# CH32V407RET-R0.net
KiCad netlist of a schematic drawn in Altium Designer
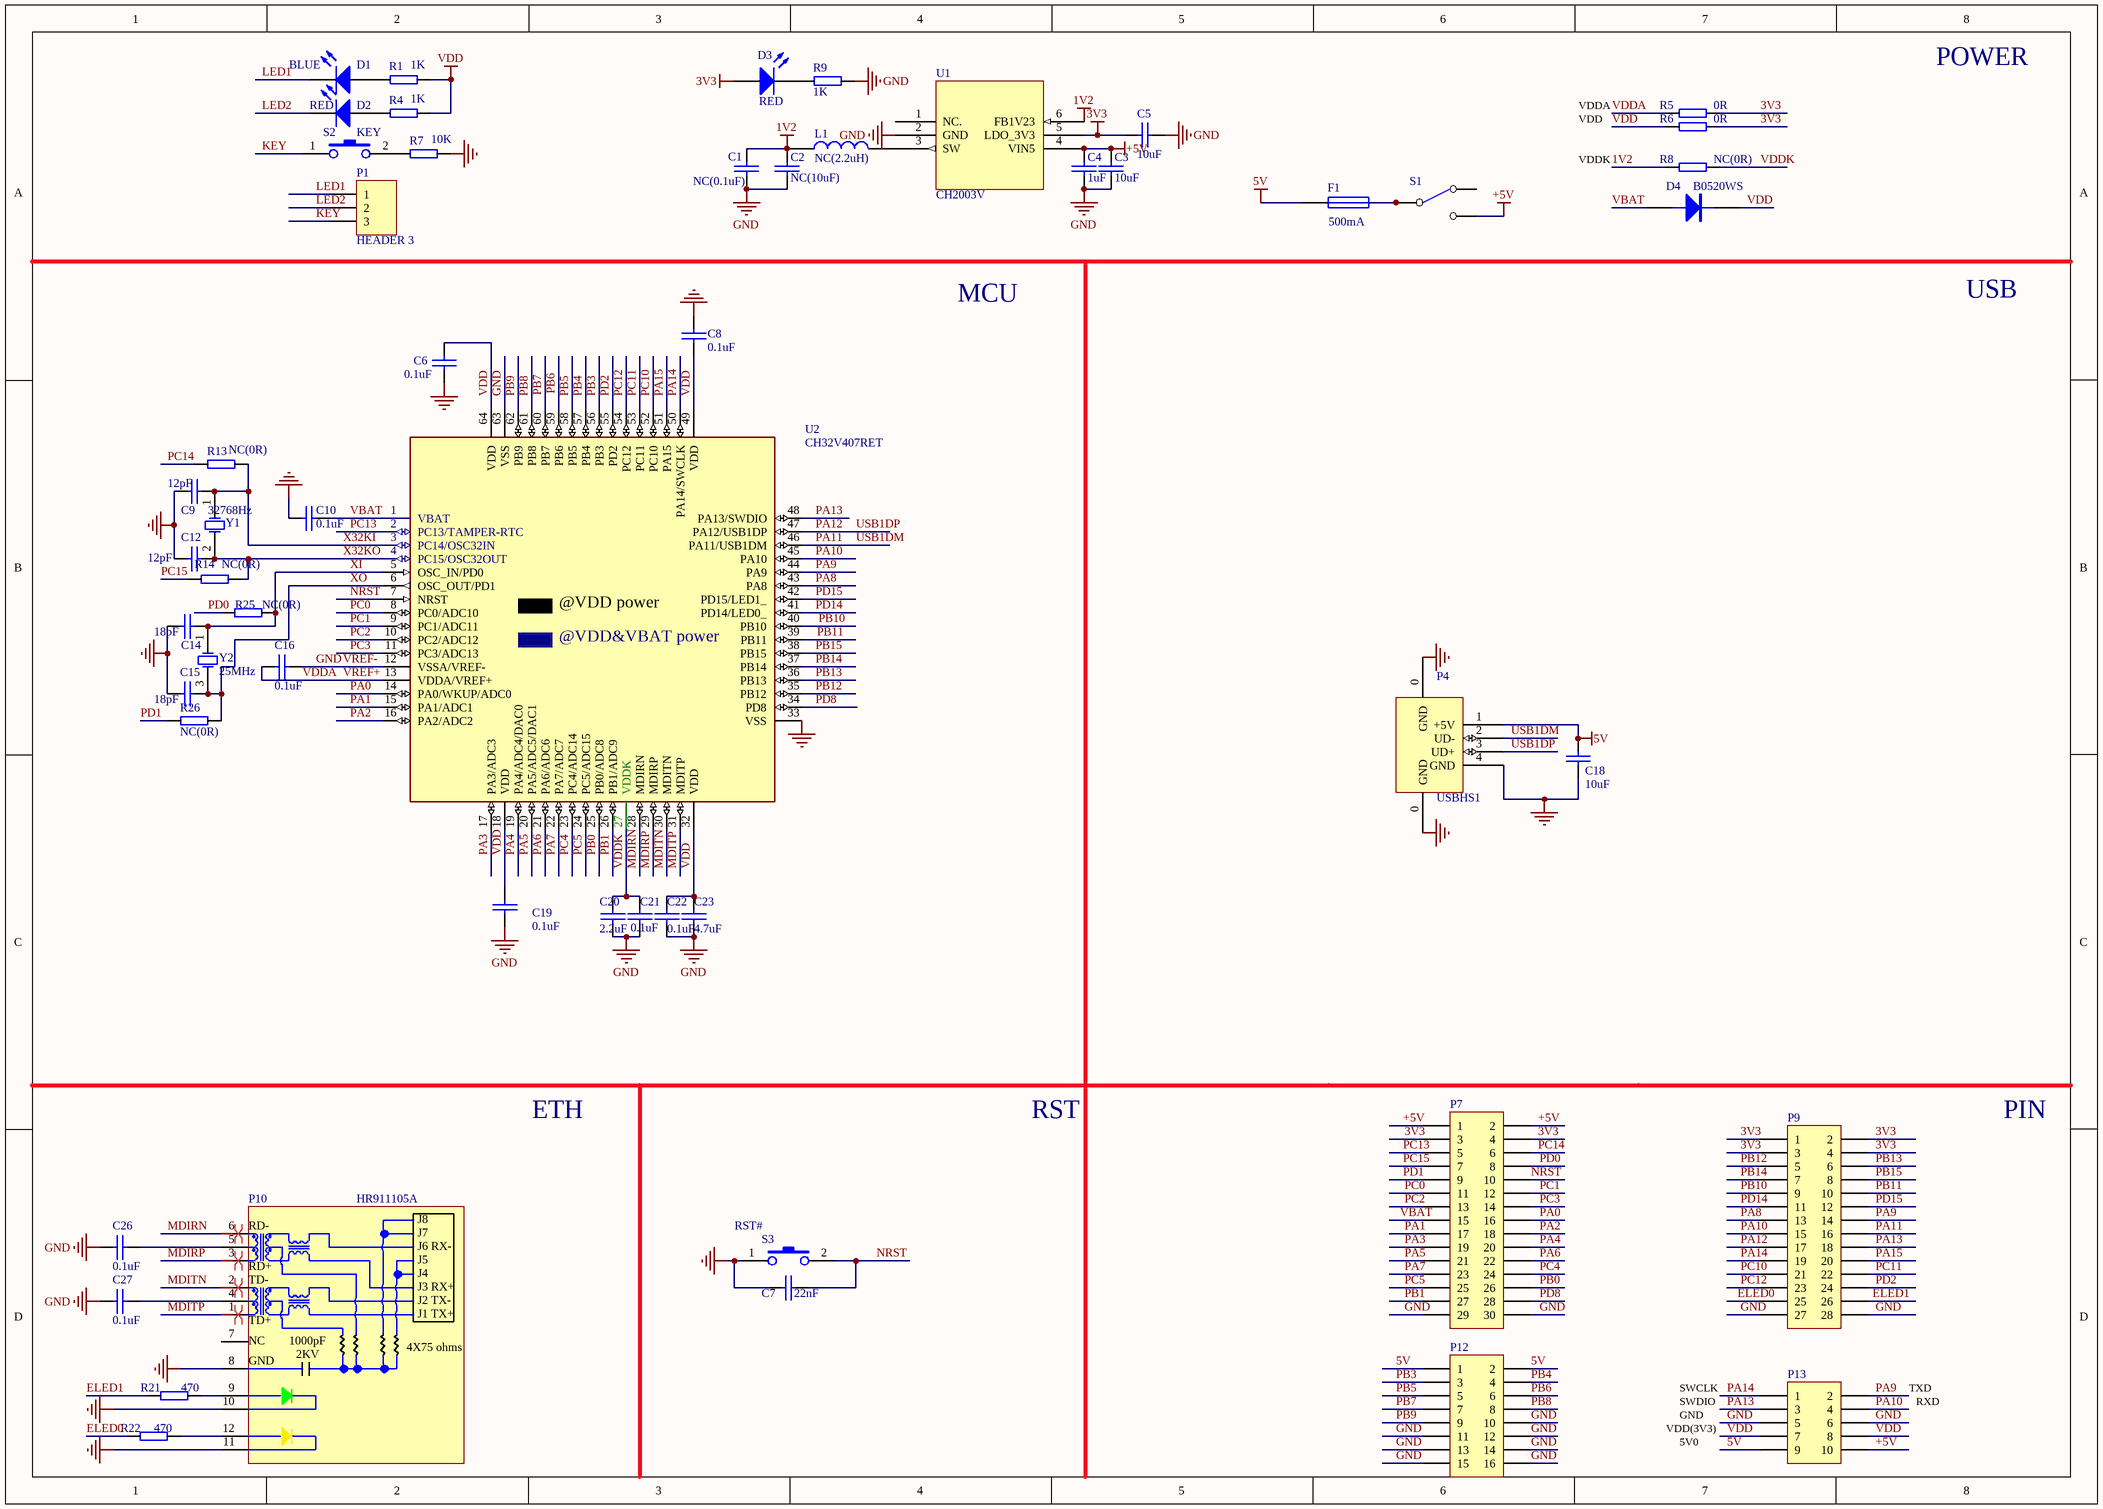
[diagram p0: CH32V407RET-R0.SchDoc]

(export (version "E")
  (design (tool "Eeschema 10.0.6"))
  (components
    (comp (ref "C1")
      (value "NC(0.1uF)")
      (footprint "0402_C")
      (description "Capacitor")
      (libsource (lib "") (part "CAP_2"))
    )
    (comp (ref "C2")
      (value "NC(10uF)")
      (footprint "0603_C")
      (description "Capacitor")
      (libsource (lib "*") (part "CAP"))
    )
    (comp (ref "C3")
      (value "10uF")
      (footprint "0603_C")
      (description "Capacitor")
      (libsource (lib "*") (part "CAP"))
    )
    (comp (ref "C4")
      (value "1uF")
      (footprint "0402_C")
      (description "Capacitor")
      (libsource (lib "") (part "CAP_2"))
    )
    (comp (ref "C5")
      (value "10uF")
      (footprint "0603_C")
      (description "Capacitor")
      (libsource (lib "*") (part "CAP"))
    )
    (comp (ref "C6")
      (value "0.1uF")
      (footprint "0402_C")
      (description "Capacitor")
      (libsource (lib "*") (part "CAP"))
    )
    (comp (ref "C7")
      (value "22nF")
      (footprint "0402_C")
      (description "Capacitor")
      (libsource (lib "") (part "CAP_1"))
    )
    (comp (ref "C8")
      (value "0.1uF")
      (footprint "0402_C")
      (description "Capacitor")
      (libsource (lib "*") (part "CAP"))
    )
    (comp (ref "C9")
      (value "12pF")
      (footprint "0402_C")
      (description "Capacitor")
      (libsource (lib "*") (part "CAP"))
    )
    (comp (ref "C10")
      (value "0.1uF")
      (footprint "0402_C")
      (description "Capacitor")
      (libsource (lib "*") (part "CAP"))
    )
    (comp (ref "C12")
      (value "12pF")
      (footprint "0402_C")
      (description "Capacitor")
      (libsource (lib "*") (part "CAP"))
    )
    (comp (ref "C14")
      (value "18pF")
      (footprint "0402_C")
      (description "Capacitor")
      (libsource (lib "*") (part "CAP"))
    )
    (comp (ref "C15")
      (value "18pF")
      (footprint "0402_C")
      (description "Capacitor")
      (libsource (lib "*") (part "CAP"))
    )
    (comp (ref "C16")
      (value "0.1uF")
      (footprint "0402_C")
      (description "Capacitor")
      (libsource (lib "*") (part "CAP"))
    )
    (comp (ref "C18")
      (value "10uF")
      (footprint "0603_C")
      (description "Capacitor")
      (libsource (lib "") (part "CAP_1"))
    )
    (comp (ref "C19")
      (value "0.1uF")
      (footprint "0402_C")
      (description "Capacitor")
      (libsource (lib "*") (part "CAP"))
    )
    (comp (ref "C20")
      (value "2.2uF")
      (footprint "0402_C")
      (description "Capacitor")
      (libsource (lib "*") (part "CAP"))
    )
    (comp (ref "C21")
      (value "0.1uF")
      (footprint "0402_C")
      (description "Capacitor")
      (libsource (lib "*") (part "CAP"))
    )
    (comp (ref "C22")
      (value "0.1uF")
      (footprint "0402_C")
      (description "Capacitor")
      (libsource (lib "*") (part "CAP"))
    )
    (comp (ref "C23")
      (value "4.7uF")
      (footprint "0402_C")
      (description "Capacitor")
      (libsource (lib "*") (part "CAP"))
    )
    (comp (ref "C26")
      (value "0.1uF")
      (footprint "0402_C")
      (description "Capacitor")
      (libsource (lib "wch_sch_others") (part "CAP"))
    )
    (comp (ref "C27")
      (value "0.1uF")
      (footprint "0402_C")
      (description "Capacitor")
      (libsource (lib "wch_sch_others") (part "CAP"))
    )
    (comp (ref "D1")
      (value "BLUE")
      (footprint "0603+")
      (description "Typical INFRARED GaAs LED")
      (fields (field (name "PUBLISHER") "Altium Limited"))
      (libsource (lib "*") (part "LED0"))
    )
    (comp (ref "D2")
      (value "RED")
      (footprint "0603+")
      (description "Typical INFRARED GaAs LED")
      (fields (field (name "PUBLISHER") "Altium Limited"))
      (libsource (lib "*") (part "LED0"))
    )
    (comp (ref "D3")
      (value "RED")
      (footprint "0603+")
      (description "Typical INFRARED GaAs LED")
      (fields (field (name "PUBLISHER") "Altium Limited"))
      (libsource (lib "*") (part "LED0"))
    )
    (comp (ref "D4")
      (value "B0520WS")
      (footprint "SOD-323")
      (description "Diode")
      (libsource (lib "*") (part "DIODE"))
    )
    (comp (ref "F1")
      (value "500mA")
      (footprint "0603")
      (description "Fuse")
      (libsource (lib "wch_sch_others") (part "FUSE1"))
    )
    (comp (ref "L1") (value "NC(2.2uH)") (footprint "CD32") (libsource (lib "*") (part "INDUCTOR")))
    (comp (ref "P1")
      (value "HEADER 3")
      (footprint "SIP3-2.54MM")
      (description "Header, 3-Pin")
      (libsource (lib "wch_sch_others") (part "HEADER 3"))
    )
    (comp (ref "P4")
      (value "USBHS1")
      (footprint "USBAF")
      (description "USB Port")
      (libsource (lib "*") (part "USB"))
    )
    (comp (ref "P7")
      (value "HEADER 15x2")
      (footprint "MYPCB:IDC30-2.54MM")
      (description "Header, 15-Pin, Dual row")
      (libsource (lib "wch_sch_others") (part "HEADER 15x2"))
    )
    (comp (ref "P9")
      (value "HEADER 14x2")
      (footprint "MYPCB:IDC28-2.54MM")
      (description "Header, 14-Pin, Dual row")
      (libsource (lib "wch_sch_others") (part "HEADER 14x2"))
    )
    (comp (ref "P10") (value "HR911105A") (footprint "HR911105A") (libsource (lib "*") (part "HR911105A")))
    (comp (ref "P12")
      (value "Ppin")
      (footprint "IDC16-2.54mm")
      (description "Header, 8-Pin, Dual row, Right Angle")
      (fields (field (name "PUBLISHER") "Altium Limited"))
      (libsource (lib "Miscellaneous Connectors") (part "Header 8X2H"))
    )
    (comp (ref "P13")
      (value "LINK")
      (footprint "IDC10-2.54mm")
      (description "Header, 5-Pin, Dual row, Right Angle")
      (fields (field (name "PUBLISHER") "Altium Limited"))
      (libsource (lib "Miscellaneous Connectors") (part "Header 5X2H"))
    )
    (comp (ref "R1") (value "1K") (footprint "0402") (libsource (lib "wch_sch_others") (part "RES")))
    (comp (ref "R4") (value "1K") (footprint "0402") (libsource (lib "wch_sch_others") (part "RES")))
    (comp (ref "R5") (value "0R") (footprint "0402") (libsource (lib "*") (part "R")))
    (comp (ref "R6") (value "0R") (footprint "0402") (libsource (lib "*") (part "R")))
    (comp (ref "R7") (value "10K") (footprint "0402") (libsource (lib "wch_sch_others") (part "RES")))
    (comp (ref "R8") (value "NC(0R)") (footprint "0402") (libsource (lib "*") (part "R")))
    (comp (ref "R9") (value "1K") (footprint "0402") (libsource (lib "wch_sch_others") (part "RES")))
    (comp (ref "R13") (value "NC(0R)") (footprint "0402") (libsource (lib "wch_sch_others") (part "RES")))
    (comp (ref "R14") (value "NC(0R)") (footprint "0402") (libsource (lib "wch_sch_others") (part "RES")))
    (comp (ref "R21") (value "470") (footprint "0402") (libsource (lib "wch_sch_others") (part "RES")))
    (comp (ref "R22") (value "470") (footprint "0402") (libsource (lib "wch_sch_others") (part "RES")))
    (comp (ref "R25") (value "NC(0R)") (footprint "0402") (libsource (lib "wch_sch_others") (part "RES")))
    (comp (ref "R26") (value "NC(0R)") (footprint "0402") (libsource (lib "wch_sch_others") (part "RES")))
    (comp (ref "S1") (value "SW SPDT") (footprint "SW1") (libsource (lib "*") (part "SW SPDT")))
    (comp (ref "S2")
      (value "KEY")
      (footprint "SMD_6.1x3.65x2.5mm-KEY")
      (libsource (lib "wch_sch_others") (part "KEY1"))
    )
    (comp (ref "S3")
      (value "RST#")
      (footprint "SMD_6.1x3.65x2.5mm-KEY")
      (libsource (lib "wch_sch_others") (part "KEY1"))
    )
    (comp (ref "U1")
      (value "CH2003V")
      (footprint "SOT-23-6")
      (description "Step-Down DC-DC Converter, 5V input, 1.23V * 800mA output, with LDO 3.3V * 200mA")
      (libsource (lib "CHXXX") (part "CH2003V"))
    )
    (comp (ref "U2")
      (value "CH32V407RET")
      (footprint "LQFP64_7X7")
      (description "RISC-V FPU HD-MCU, 175MHz, USB_480M, 100M Ethernet & Phy, CAN, ADC, DAC")
      (libsource (lib "DHXXXSCH") (part "CH32V407RET"))
    )
    (comp (ref "Y1")
      (value "32768Hz")
      (footprint "FC-135")
      (description "Crystal Oscillator")
      (fields (field (name "PUBLISHER") "Altium Limited"))
      (libsource (lib "") (part "XTAL_1"))
    )
    (comp (ref "Y2")
      (value "25MHz")
      (footprint "XT3225")
      (description "Crystal Oscillator")
      (fields (field (name "PUBLISHER") "Altium Limited"))
      (libsource (lib "*") (part "XTAL"))
    )
  )
  (nets
    (net (code "1") (name "+5V") (class "Default")
      (node (ref "C3") (pin "2") (pinfunction "2_2") (pintype "passive"))
      (node (ref "C4") (pin "2") (pinfunction "2_2") (pintype "passive"))
      (node (ref "P13") (pin "10") (pinfunction "10_10") (pintype "passive"))
      (node (ref "P7") (pin "1") (pinfunction "1_1") (pintype "passive"))
      (node (ref "P7") (pin "2") (pinfunction "2_2") (pintype "passive"))
      (node (ref "S1") (pin "2") (pinfunction "NC_2") (pintype "passive"))
      (node (ref "U1") (pin "4") (pinfunction "VIN5_4") (pintype "power_in"))
    )
    (net (code "3") (name "/ELED0") (class "Default")
      (node (ref "P9") (pin "25") (pinfunction "25_25") (pintype "passive"))
      (node (ref "R22") (pin "1") (pintype "passive"))
    )
    (net (code "4") (name "/ELED1") (class "Default")
      (node (ref "P9") (pin "26") (pinfunction "26_26") (pintype "passive"))
      (node (ref "R21") (pin "1") (pintype "passive"))
    )
    (net (code "5") (name "/KEY") (class "Default")
      (node (ref "P1") (pin "3") (pinfunction "3_3") (pintype "passive"))
      (node (ref "S2") (pin "1") (pinfunction "1_1") (pintype "passive"))
    )
    (net (code "6") (name "/LED1") (class "Default")
      (node (ref "D1") (pin "2") (pinfunction "K_2") (pintype "passive"))
      (node (ref "P1") (pin "1") (pinfunction "1_1") (pintype "passive"))
    )
    (net (code "7") (name "/LED2") (class "Default")
      (node (ref "D2") (pin "2") (pinfunction "K_2") (pintype "passive"))
      (node (ref "P1") (pin "2") (pinfunction "2_2") (pintype "passive"))
    )
    (net (code "8") (name "/MDIRN") (class "Default")
      (node (ref "P10") (pin "6") (pintype "passive"))
      (node (ref "U2") (pin "28") (pinfunction "MDIRN_28") (pintype "bidirectional"))
    )
    (net (code "9") (name "/MDIRP") (class "Default")
      (node (ref "P10") (pin "3") (pintype "passive"))
      (node (ref "U2") (pin "29") (pinfunction "MDIRP_29") (pintype "bidirectional"))
    )
    (net (code "10") (name "/MDITN") (class "Default")
      (node (ref "P10") (pin "2") (pintype "passive"))
      (node (ref "U2") (pin "30") (pinfunction "MDITN_30") (pintype "bidirectional"))
    )
    (net (code "11") (name "/MDITP") (class "Default")
      (node (ref "P10") (pin "1") (pintype "passive"))
      (node (ref "U2") (pin "31") (pinfunction "MDITP_31") (pintype "bidirectional"))
    )
    (net (code "12") (name "/NRST") (class "Default")
      (node (ref "C7") (pin "2") (pinfunction "2_2") (pintype "passive"))
      (node (ref "P7") (pin "10") (pinfunction "10_10") (pintype "passive"))
      (node (ref "S3") (pin "2") (pinfunction "2_2") (pintype "passive"))
      (node (ref "U2") (pin "7") (pinfunction "NRST_7") (pintype "input"))
    )
    (net (code "13") (name "/PA0") (class "Default")
      (node (ref "P7") (pin "16") (pinfunction "16_16") (pintype "passive"))
      (node (ref "U2") (pin "14") (pinfunction "PA0/WKUP/ADC0_14") (pintype "bidirectional"))
    )
    (net (code "14") (name "/PA1") (class "Default")
      (node (ref "P7") (pin "17") (pinfunction "17_17") (pintype "passive"))
      (node (ref "U2") (pin "15") (pinfunction "PA1/ADC1_15") (pintype "bidirectional"))
    )
    (net (code "15") (name "/PA2") (class "Default")
      (node (ref "P7") (pin "18") (pinfunction "18_18") (pintype "passive"))
      (node (ref "U2") (pin "16") (pinfunction "PA2/ADC2_16") (pintype "bidirectional"))
    )
    (net (code "16") (name "/PA3") (class "Default")
      (node (ref "P7") (pin "19") (pinfunction "19_19") (pintype "passive"))
      (node (ref "U2") (pin "17") (pinfunction "PA3/ADC3_17") (pintype "bidirectional"))
    )
    (net (code "17") (name "/PA4") (class "Default")
      (node (ref "P7") (pin "20") (pinfunction "20_20") (pintype "passive"))
      (node (ref "U2") (pin "19") (pinfunction "PA4/ADC4/DAC0_19") (pintype "bidirectional"))
    )
    (net (code "18") (name "/PA5") (class "Default")
      (node (ref "P7") (pin "21") (pinfunction "21_21") (pintype "passive"))
      (node (ref "U2") (pin "20") (pinfunction "PA5/ADC5/DAC1_20") (pintype "bidirectional"))
    )
    (net (code "19") (name "/PA6") (class "Default")
      (node (ref "P7") (pin "22") (pinfunction "22_22") (pintype "passive"))
      (node (ref "U2") (pin "21") (pinfunction "PA6/ADC6_21") (pintype "bidirectional"))
    )
    (net (code "20") (name "/PA7") (class "Default")
      (node (ref "P7") (pin "23") (pinfunction "23_23") (pintype "passive"))
      (node (ref "U2") (pin "22") (pinfunction "PA7/ADC7_22") (pintype "bidirectional"))
    )
    (net (code "21") (name "/PA8") (class "Default")
      (node (ref "P9") (pin "13") (pinfunction "13_13") (pintype "passive"))
      (node (ref "U2") (pin "43") (pinfunction "PA8_43") (pintype "bidirectional"))
    )
    (net (code "22") (name "/PA9") (class "Default")
      (node (ref "P13") (pin "2") (pinfunction "2_2") (pintype "passive"))
      (node (ref "P9") (pin "14") (pinfunction "14_14") (pintype "passive"))
      (node (ref "U2") (pin "44") (pinfunction "PA9_44") (pintype "bidirectional"))
    )
    (net (code "23") (name "/PA10") (class "Default")
      (node (ref "P13") (pin "4") (pinfunction "4_4") (pintype "passive"))
      (node (ref "P9") (pin "15") (pinfunction "15_15") (pintype "passive"))
      (node (ref "U2") (pin "45") (pinfunction "PA10_45") (pintype "bidirectional"))
    )
    (net (code "24") (name "/PA11") (class "Default")
      (node (ref "P4") (pin "2") (pinfunction "UD-_2") (pintype "bidirectional"))
      (node (ref "P9") (pin "16") (pinfunction "16_16") (pintype "passive"))
      (node (ref "U2") (pin "46") (pinfunction "PA11/USB1DM_46") (pintype "bidirectional"))
    )
    (net (code "25") (name "/PA12") (class "Default")
      (node (ref "P4") (pin "3") (pinfunction "UD+_3") (pintype "bidirectional"))
      (node (ref "P9") (pin "17") (pinfunction "17_17") (pintype "passive"))
      (node (ref "U2") (pin "47") (pinfunction "PA12/USB1DP_47") (pintype "bidirectional"))
    )
    (net (code "26") (name "/PA13") (class "Default")
      (node (ref "P13") (pin "3") (pinfunction "3_3") (pintype "passive"))
      (node (ref "P9") (pin "18") (pinfunction "18_18") (pintype "passive"))
      (node (ref "U2") (pin "48") (pinfunction "PA13/SWDIO_48") (pintype "bidirectional"))
    )
    (net (code "27") (name "/PA14") (class "Default")
      (node (ref "P13") (pin "1") (pinfunction "1_1") (pintype "passive"))
      (node (ref "P9") (pin "19") (pinfunction "19_19") (pintype "passive"))
      (node (ref "U2") (pin "50") (pinfunction "PA14/SWCLK_50") (pintype "bidirectional"))
    )
    (net (code "28") (name "/PA15") (class "Default")
      (node (ref "P9") (pin "20") (pinfunction "20_20") (pintype "passive"))
      (node (ref "U2") (pin "51") (pinfunction "PA15_51") (pintype "bidirectional"))
    )
    (net (code "29") (name "/PB0") (class "Default")
      (node (ref "P7") (pin "26") (pinfunction "26_26") (pintype "passive"))
      (node (ref "U2") (pin "25") (pinfunction "PB0/ADC8_25") (pintype "bidirectional"))
    )
    (net (code "30") (name "/PB1") (class "Default")
      (node (ref "P7") (pin "27") (pinfunction "27_27") (pintype "passive"))
      (node (ref "U2") (pin "26") (pinfunction "PB1/ADC9_26") (pintype "bidirectional"))
    )
    (net (code "31") (name "/PB3") (class "Default")
      (node (ref "P12") (pin "3") (pinfunction "3_3") (pintype "passive"))
      (node (ref "U2") (pin "56") (pinfunction "PB3_56") (pintype "bidirectional"))
    )
    (net (code "32") (name "/PB4") (class "Default")
      (node (ref "P12") (pin "4") (pinfunction "4_4") (pintype "passive"))
      (node (ref "U2") (pin "57") (pinfunction "PB4_57") (pintype "bidirectional"))
    )
    (net (code "33") (name "/PB5") (class "Default")
      (node (ref "P12") (pin "5") (pinfunction "5_5") (pintype "passive"))
      (node (ref "U2") (pin "58") (pinfunction "PB5_58") (pintype "bidirectional"))
    )
    (net (code "34") (name "/PB6") (class "Default")
      (node (ref "P12") (pin "6") (pinfunction "6_6") (pintype "passive"))
      (node (ref "U2") (pin "59") (pinfunction "PB6_59") (pintype "bidirectional"))
    )
    (net (code "35") (name "/PB7") (class "Default")
      (node (ref "P12") (pin "7") (pinfunction "7_7") (pintype "passive"))
      (node (ref "U2") (pin "60") (pinfunction "PB7_60") (pintype "bidirectional"))
    )
    (net (code "36") (name "/PB8") (class "Default")
      (node (ref "P12") (pin "8") (pinfunction "8_8") (pintype "passive"))
      (node (ref "U2") (pin "61") (pinfunction "PB8_61") (pintype "bidirectional"))
    )
    (net (code "37") (name "/PB9") (class "Default")
      (node (ref "P12") (pin "9") (pinfunction "9_9") (pintype "passive"))
      (node (ref "U2") (pin "62") (pinfunction "PB9_62") (pintype "bidirectional"))
    )
    (net (code "38") (name "/PB10") (class "Default")
      (node (ref "P9") (pin "9") (pinfunction "9_9") (pintype "passive"))
      (node (ref "U2") (pin "40") (pinfunction "PB10_40") (pintype "bidirectional"))
    )
    (net (code "39") (name "/PB11") (class "Default")
      (node (ref "P9") (pin "10") (pinfunction "10_10") (pintype "passive"))
      (node (ref "U2") (pin "39") (pinfunction "PB11_39") (pintype "bidirectional"))
    )
    (net (code "40") (name "/PB12") (class "Default")
      (node (ref "P9") (pin "5") (pinfunction "5_5") (pintype "passive"))
      (node (ref "U2") (pin "35") (pinfunction "PB12_35") (pintype "bidirectional"))
    )
    (net (code "41") (name "/PB13") (class "Default")
      (node (ref "P9") (pin "6") (pinfunction "6_6") (pintype "passive"))
      (node (ref "U2") (pin "36") (pinfunction "PB13_36") (pintype "bidirectional"))
    )
    (net (code "42") (name "/PB14") (class "Default")
      (node (ref "P9") (pin "7") (pinfunction "7_7") (pintype "passive"))
      (node (ref "U2") (pin "37") (pinfunction "PB14_37") (pintype "bidirectional"))
    )
    (net (code "43") (name "/PB15") (class "Default")
      (node (ref "P9") (pin "8") (pinfunction "8_8") (pintype "passive"))
      (node (ref "U2") (pin "38") (pinfunction "PB15_38") (pintype "bidirectional"))
    )
    (net (code "44") (name "/PC0") (class "Default")
      (node (ref "P7") (pin "11") (pinfunction "11_11") (pintype "passive"))
      (node (ref "U2") (pin "8") (pinfunction "PC0/ADC10_8") (pintype "bidirectional"))
    )
    (net (code "45") (name "/PC1") (class "Default")
      (node (ref "P7") (pin "12") (pinfunction "12_12") (pintype "passive"))
      (node (ref "U2") (pin "9") (pinfunction "PC1/ADC11_9") (pintype "bidirectional"))
    )
    (net (code "46") (name "/PC2") (class "Default")
      (node (ref "P7") (pin "13") (pinfunction "13_13") (pintype "passive"))
      (node (ref "U2") (pin "10") (pinfunction "PC2/ADC12_10") (pintype "bidirectional"))
    )
    (net (code "47") (name "/PC3") (class "Default")
      (node (ref "P7") (pin "14") (pinfunction "14_14") (pintype "passive"))
      (node (ref "U2") (pin "11") (pinfunction "PC3/ADC13_11") (pintype "bidirectional"))
    )
    (net (code "48") (name "/PC4") (class "Default")
      (node (ref "P7") (pin "24") (pinfunction "24_24") (pintype "passive"))
      (node (ref "U2") (pin "23") (pinfunction "PC4/ADC14_23") (pintype "bidirectional"))
    )
    (net (code "49") (name "/PC5") (class "Default")
      (node (ref "P7") (pin "25") (pinfunction "25_25") (pintype "passive"))
      (node (ref "U2") (pin "24") (pinfunction "PC5/ADC15_24") (pintype "bidirectional"))
    )
    (net (code "50") (name "/PC10") (class "Default")
      (node (ref "P9") (pin "21") (pinfunction "21_21") (pintype "passive"))
      (node (ref "U2") (pin "52") (pinfunction "PC10_52") (pintype "bidirectional"))
    )
    (net (code "51") (name "/PC11") (class "Default")
      (node (ref "P9") (pin "22") (pinfunction "22_22") (pintype "passive"))
      (node (ref "U2") (pin "53") (pinfunction "PC11_53") (pintype "bidirectional"))
    )
    (net (code "52") (name "/PC12") (class "Default")
      (node (ref "P9") (pin "23") (pinfunction "23_23") (pintype "passive"))
      (node (ref "U2") (pin "54") (pinfunction "PC12_54") (pintype "bidirectional"))
    )
    (net (code "53") (name "/PC13") (class "Default")
      (node (ref "P7") (pin "5") (pinfunction "5_5") (pintype "passive"))
      (node (ref "U2") (pin "2") (pinfunction "PC13/TAMPER-RTC_2") (pintype "bidirectional"))
    )
    (net (code "54") (name "/PC14") (class "Default")
      (node (ref "P7") (pin "6") (pinfunction "6_6") (pintype "passive"))
      (node (ref "R13") (pin "1") (pintype "passive"))
    )
    (net (code "55") (name "/PC15") (class "Default")
      (node (ref "P7") (pin "7") (pinfunction "7_7") (pintype "passive"))
      (node (ref "R14") (pin "1") (pintype "passive"))
    )
    (net (code "56") (name "/PD0") (class "Default")
      (node (ref "P7") (pin "8") (pinfunction "8_8") (pintype "passive"))
      (node (ref "R25") (pin "1") (pintype "passive"))
    )
    (net (code "57") (name "/PD1") (class "Default")
      (node (ref "P7") (pin "9") (pinfunction "9_9") (pintype "passive"))
      (node (ref "R26") (pin "2") (pintype "passive"))
    )
    (net (code "58") (name "/PD2") (class "Default")
      (node (ref "P9") (pin "24") (pinfunction "24_24") (pintype "passive"))
      (node (ref "U2") (pin "55") (pinfunction "PD2_55") (pintype "bidirectional"))
    )
    (net (code "59") (name "/PD8") (class "Default")
      (node (ref "P7") (pin "28") (pinfunction "28_28") (pintype "passive"))
      (node (ref "U2") (pin "34") (pinfunction "PD8_34") (pintype "bidirectional"))
    )
    (net (code "60") (name "/PD14") (class "Default")
      (node (ref "P9") (pin "11") (pinfunction "11_11") (pintype "passive"))
      (node (ref "U2") (pin "41") (pinfunction "PD14/LED0__41") (pintype "bidirectional"))
    )
    (net (code "61") (name "/PD15") (class "Default")
      (node (ref "P9") (pin "12") (pinfunction "12_12") (pintype "passive"))
      (node (ref "U2") (pin "42") (pinfunction "PD15/LED1__42") (pintype "bidirectional"))
    )
    (net (code "62") (name "/VBAT") (class "Default")
      (node (ref "C10") (pin "2") (pinfunction "2_2") (pintype "passive"))
      (node (ref "D4") (pin "1") (pinfunction "A_1") (pintype "passive"))
      (node (ref "P7") (pin "15") (pinfunction "15_15") (pintype "passive"))
      (node (ref "U2") (pin "1") (pinfunction "VBAT_1") (pintype "power_in"))
    )
    (net (code "63") (name "/VDDA") (class "Default")
      (node (ref "C16") (pin "1") (pinfunction "1_1") (pintype "passive"))
      (node (ref "R5") (pin "2") (pinfunction "2_2") (pintype "passive"))
      (node (ref "U2") (pin "13") (pinfunction "VDDA/VREF+_13") (pintype "power_in"))
    )
    (net (code "64") (name "/VDDK") (class "Default")
      (node (ref "C20") (pin "2") (pinfunction "2_2") (pintype "passive"))
      (node (ref "C21") (pin "2") (pinfunction "2_2") (pintype "passive"))
      (node (ref "R8") (pin "1") (pinfunction "1_1") (pintype "passive"))
      (node (ref "U2") (pin "27") (pinfunction "VDDK_27") (pintype "power_in"))
    )
    (net (code "65") (name "/X32KI") (class "Default")
      (node (ref "C9") (pin "2") (pinfunction "2_2") (pintype "passive"))
      (node (ref "R13") (pin "2") (pintype "passive"))
      (node (ref "U2") (pin "3") (pinfunction "PC14/OSC32IN_3") (pintype "bidirectional"))
      (node (ref "Y1") (pin "1") (pinfunction "OSC1_1") (pintype "passive"))
    )
    (net (code "66") (name "/X32KO") (class "Default")
      (node (ref "C12") (pin "2") (pinfunction "2_2") (pintype "passive"))
      (node (ref "R14") (pin "2") (pintype "passive"))
      (node (ref "U2") (pin "4") (pinfunction "PC15/OSC32OUT_4") (pintype "bidirectional"))
      (node (ref "Y1") (pin "2") (pinfunction "OSC2_2") (pintype "passive"))
    )
    (net (code "67") (name "/XI") (class "Default")
      (node (ref "C14") (pin "2") (pinfunction "2_2") (pintype "passive"))
      (node (ref "R25") (pin "2") (pintype "passive"))
      (node (ref "U2") (pin "5") (pinfunction "OSC_IN/PD0_5") (pintype "input"))
      (node (ref "Y2") (pin "1") (pinfunction "OSC1_1") (pintype "passive"))
    )
    (net (code "68") (name "/XO") (class "Default")
      (node (ref "C15") (pin "2") (pinfunction "2_2") (pintype "passive"))
      (node (ref "R26") (pin "1") (pintype "passive"))
      (node (ref "U2") (pin "6") (pinfunction "OSC_OUT/PD1_6") (pintype "output"))
      (node (ref "Y2") (pin "3") (pinfunction "OSC2_3") (pintype "passive"))
    )
    (net (code "69") (name "1V2") (class "Default")
      (node (ref "C1") (pin "2") (pinfunction "2_2") (pintype "passive"))
      (node (ref "C2") (pin "2") (pinfunction "2_2") (pintype "passive"))
      (node (ref "L1") (pin "2") (pinfunction "2_2") (pintype "passive"))
      (node (ref "R8") (pin "2") (pinfunction "2_2") (pintype "passive"))
      (node (ref "U1") (pin "6") (pinfunction "FB1V23_6") (pintype "input"))
    )
    (net (code "70") (name "3V3") (class "Default")
      (node (ref "C5") (pin "2") (pinfunction "2_2") (pintype "passive"))
      (node (ref "D3") (pin "1") (pinfunction "A_1") (pintype "passive"))
      (node (ref "P7") (pin "3") (pinfunction "3_3") (pintype "passive"))
      (node (ref "P7") (pin "4") (pinfunction "4_4") (pintype "passive"))
      (node (ref "P9") (pin "1") (pinfunction "1_1") (pintype "passive"))
      (node (ref "P9") (pin "2") (pinfunction "2_2") (pintype "passive"))
      (node (ref "P9") (pin "3") (pinfunction "3_3") (pintype "passive"))
      (node (ref "P9") (pin "4") (pinfunction "4_4") (pintype "passive"))
      (node (ref "R5") (pin "1") (pinfunction "1_1") (pintype "passive"))
      (node (ref "R6") (pin "1") (pinfunction "1_1") (pintype "passive"))
      (node (ref "U1") (pin "5") (pinfunction "LDO_3V3_5") (pintype "power_in"))
    )
    (net (code "71") (name "5V") (class "Default")
      (node (ref "C18") (pin "1") (pinfunction "1_1") (pintype "passive"))
      (node (ref "F1") (pin "1") (pinfunction "1_1") (pintype "passive"))
      (node (ref "P12") (pin "1") (pinfunction "1_1") (pintype "passive"))
      (node (ref "P12") (pin "2") (pinfunction "2_2") (pintype "passive"))
      (node (ref "P13") (pin "9") (pinfunction "9_9") (pintype "passive"))
      (node (ref "P4") (pin "1") (pinfunction "+5V_1") (pintype "power_in"))
    )
    (net (code "72") (name "GND") (class "Default")
      (node (ref "C1") (pin "1") (pinfunction "1_1") (pintype "passive"))
      (node (ref "C10") (pin "1") (pinfunction "1_1") (pintype "passive"))
      (node (ref "C12") (pin "1") (pinfunction "1_1") (pintype "passive"))
      (node (ref "C14") (pin "1") (pinfunction "1_1") (pintype "passive"))
      (node (ref "C15") (pin "1") (pinfunction "1_1") (pintype "passive"))
      (node (ref "C16") (pin "2") (pinfunction "2_2") (pintype "passive"))
      (node (ref "C18") (pin "2") (pinfunction "2_2") (pintype "passive"))
      (node (ref "C19") (pin "1") (pinfunction "1_1") (pintype "passive"))
      (node (ref "C2") (pin "1") (pinfunction "1_1") (pintype "passive"))
      (node (ref "C20") (pin "1") (pinfunction "1_1") (pintype "passive"))
      (node (ref "C21") (pin "1") (pinfunction "1_1") (pintype "passive"))
      (node (ref "C22") (pin "1") (pinfunction "1_1") (pintype "passive"))
      (node (ref "C23") (pin "1") (pinfunction "1_1") (pintype "passive"))
      (node (ref "C26") (pin "1") (pinfunction "1_1") (pintype "passive"))
      (node (ref "C27") (pin "1") (pinfunction "1_1") (pintype "passive"))
      (node (ref "C3") (pin "1") (pinfunction "1_1") (pintype "passive"))
      (node (ref "C4") (pin "1") (pinfunction "1_1") (pintype "passive"))
      (node (ref "C5") (pin "1") (pinfunction "1_1") (pintype "passive"))
      (node (ref "C6") (pin "1") (pinfunction "1_1") (pintype "passive"))
      (node (ref "C7") (pin "1") (pinfunction "1_1") (pintype "passive"))
      (node (ref "C8") (pin "2") (pinfunction "2_2") (pintype "passive"))
      (node (ref "C9") (pin "1") (pinfunction "1_1") (pintype "passive"))
      (node (ref "P10") (pin "10") (pintype "passive"))
      (node (ref "P10") (pin "11") (pintype "passive"))
      (node (ref "P10") (pin "8") (pintype "passive"))
      (node (ref "P12") (pin "10") (pinfunction "10_10") (pintype "passive"))
      (node (ref "P12") (pin "11") (pinfunction "11_11") (pintype "passive"))
      (node (ref "P12") (pin "12") (pinfunction "12_12") (pintype "passive"))
      (node (ref "P12") (pin "13") (pinfunction "13_13") (pintype "passive"))
      (node (ref "P12") (pin "14") (pinfunction "14_14") (pintype "passive"))
      (node (ref "P12") (pin "15") (pinfunction "15_15") (pintype "passive"))
      (node (ref "P12") (pin "16") (pinfunction "16_16") (pintype "passive"))
      (node (ref "P13") (pin "5") (pinfunction "5_5") (pintype "passive"))
      (node (ref "P13") (pin "6") (pinfunction "6_6") (pintype "passive"))
      (node (ref "P4") (pin "0") (pinfunction "GND_0") (pintype "power_in"))
      (node (ref "P4") (pin "4") (pinfunction "GND_4") (pintype "power_in"))
      (node (ref "P7") (pin "29") (pinfunction "29_29") (pintype "passive"))
      (node (ref "P7") (pin "30") (pinfunction "30_30") (pintype "passive"))
      (node (ref "P9") (pin "27") (pinfunction "27_27") (pintype "passive"))
      (node (ref "P9") (pin "28") (pinfunction "28_28") (pintype "passive"))
      (node (ref "R7") (pin "1") (pintype "passive"))
      (node (ref "R9") (pin "2") (pintype "passive"))
      (node (ref "S3") (pin "1") (pinfunction "1_1") (pintype "passive"))
      (node (ref "U1") (pin "2") (pinfunction "GND_2") (pintype "power_in"))
      (node (ref "U2") (pin "12") (pinfunction "VSSA/VREF-_12") (pintype "power_in"))
      (node (ref "U2") (pin "33") (pinfunction "VSS_33") (pintype "power_in"))
      (node (ref "U2") (pin "63") (pinfunction "VSS_63") (pintype "power_in"))
    )
    (net (code "73") (name "Net-(C26-Pad2)") (class "Default")
      (node (ref "C26") (pin "2") (pinfunction "2_2") (pintype "passive"))
      (node (ref "P10") (pin "5") (pintype "passive"))
    )
    (net (code "74") (name "Net-(C27-Pad2)") (class "Default")
      (node (ref "C27") (pin "2") (pinfunction "2_2") (pintype "passive"))
      (node (ref "P10") (pin "4") (pintype "passive"))
    )
    (net (code "75") (name "Net-(D1-A)") (class "Default")
      (node (ref "D1") (pin "1") (pinfunction "A_1") (pintype "passive"))
      (node (ref "R1") (pin "2") (pintype "passive"))
    )
    (net (code "76") (name "Net-(D2-A)") (class "Default")
      (node (ref "D2") (pin "1") (pinfunction "A_1") (pintype "passive"))
      (node (ref "R4") (pin "2") (pintype "passive"))
    )
    (net (code "77") (name "Net-(D3-K)") (class "Default")
      (node (ref "D3") (pin "2") (pinfunction "K_2") (pintype "passive"))
      (node (ref "R9") (pin "1") (pintype "passive"))
    )
    (net (code "78") (name "Net-(P10-Pad9)") (class "Default")
      (node (ref "P10") (pin "9") (pintype "passive"))
      (node (ref "R21") (pin "2") (pintype "passive"))
    )
    (net (code "79") (name "Net-(P10-Pad12)") (class "Default")
      (node (ref "P10") (pin "12") (pintype "passive"))
      (node (ref "R22") (pin "2") (pintype "passive"))
    )
    (net (code "80") (name "Net-(R7-Pad2)") (class "Default")
      (node (ref "R7") (pin "2") (pintype "passive"))
      (node (ref "S2") (pin "2") (pinfunction "2_2") (pintype "passive"))
    )
    (net (code "81") (name "Net-(S1-COMMON)") (class "Default")
      (node (ref "F1") (pin "2") (pinfunction "2_2") (pintype "passive"))
      (node (ref "S1") (pin "1") (pinfunction "COMMON_1") (pintype "passive"))
    )
    (net (code "82") (name "Net-(U1-SW)") (class "Default")
      (node (ref "L1") (pin "1") (pinfunction "1_1") (pintype "passive"))
      (node (ref "U1") (pin "3") (pinfunction "SW_3") (pintype "output"))
    )
    (net (code "83") (name "VDD") (class "Default")
      (node (ref "C19") (pin "2") (pinfunction "2_2") (pintype "passive"))
      (node (ref "C22") (pin "2") (pinfunction "2_2") (pintype "passive"))
      (node (ref "C23") (pin "2") (pinfunction "2_2") (pintype "passive"))
      (node (ref "C6") (pin "2") (pinfunction "2_2") (pintype "passive"))
      (node (ref "C8") (pin "1") (pinfunction "1_1") (pintype "passive"))
      (node (ref "D4") (pin "2") (pinfunction "K_2") (pintype "passive"))
      (node (ref "P13") (pin "7") (pinfunction "7_7") (pintype "passive"))
      (node (ref "P13") (pin "8") (pinfunction "8_8") (pintype "passive"))
      (node (ref "R1") (pin "1") (pintype "passive"))
      (node (ref "R4") (pin "1") (pintype "passive"))
      (node (ref "R6") (pin "2") (pinfunction "2_2") (pintype "passive"))
      (node (ref "U2") (pin "18") (pinfunction "VDD_18") (pintype "power_in"))
      (node (ref "U2") (pin "32") (pinfunction "VDD_32") (pintype "power_in"))
      (node (ref "U2") (pin "49") (pinfunction "VDD_49") (pintype "power_in"))
      (node (ref "U2") (pin "64") (pinfunction "VDD_64") (pintype "power_in"))
    )
    (net (code "84") (name "unconnected-(P10-Pad7)") (class "Default")
      (node (ref "P10") (pin "7") (pintype "passive"))
    )
    (net (code "85") (name "unconnected-(S1-NO-Pad3)") (class "Default")
      (node (ref "S1") (pin "3") (pinfunction "NO_3") (pintype "passive"))
    )
    (net (code "86") (name "unconnected-(U1-NC.-Pad1)") (class "Default")
      (node (ref "U1") (pin "1") (pinfunction "NC._1") (pintype "passive"))
    )
  )
)
